# LoRa_ST_Sensor_Node_v1_2.net
KiCad netlist of a schematic drawn in EAGLE
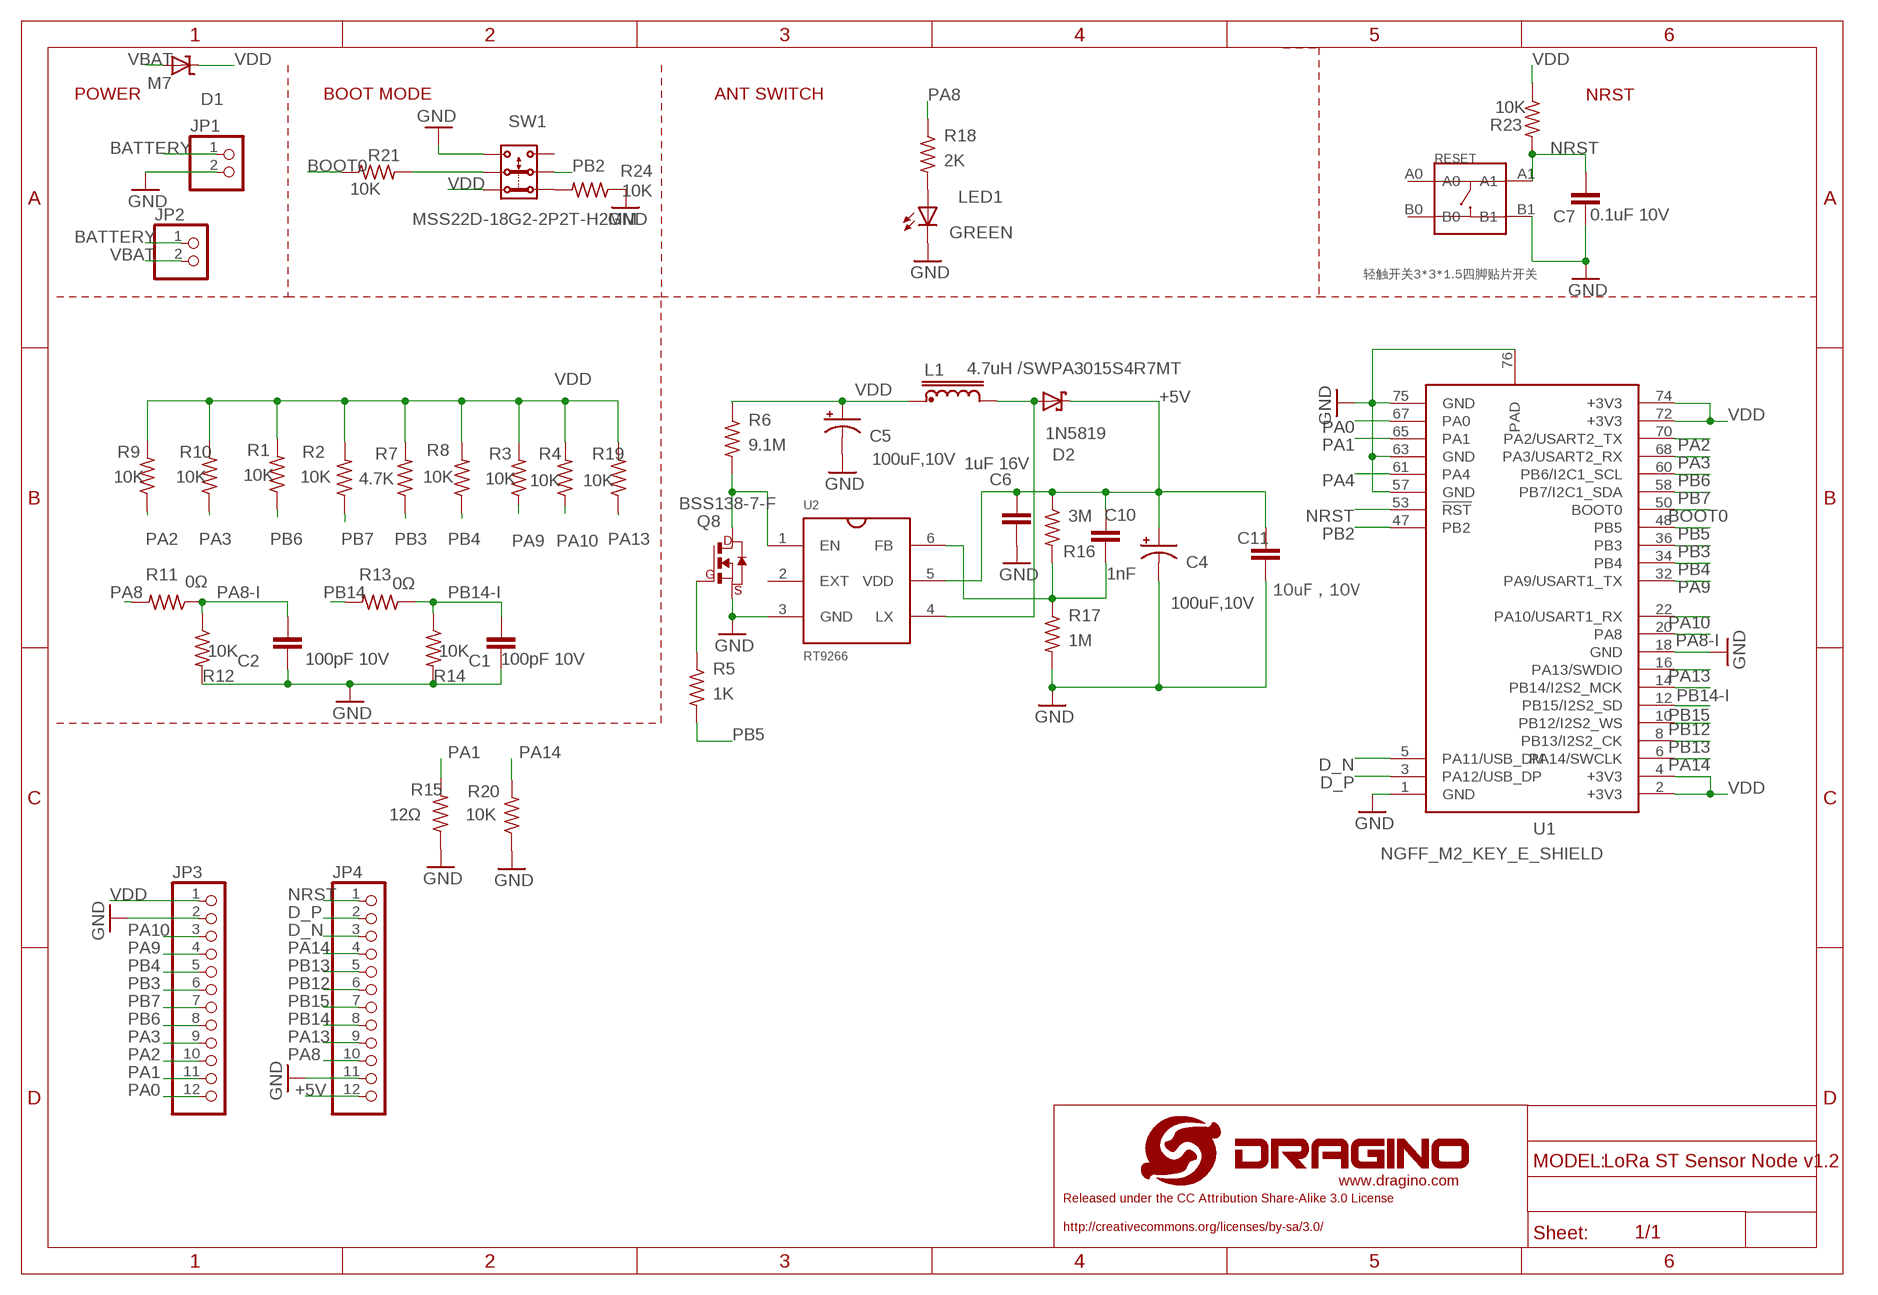
[diagram p0: schematic, sheet 1]

(export (version "E")
  (design (tool "Eeschema 10.0.6"))
  (components
    (comp (ref "C1")
      (value "100pF 10V")
      (footprint "eagle-import:C0603")
      (libsource (lib "eagle-import") (part "C-EUC0603"))
    )
    (comp (ref "C2")
      (value "100pF 10V")
      (footprint "eagle-import:C0603")
      (libsource (lib "eagle-import") (part "C-EUC0603"))
    )
    (comp (ref "C4")
      (value "100uF,10V")
      (footprint "eagle-import:SMC_B")
      (libsource (lib "eagle-import") (part "CPOL-USSMCB"))
    )
    (comp (ref "C5")
      (value "100uF,10V")
      (footprint "eagle-import:SMC_B")
      (libsource (lib "eagle-import") (part "CPOL-USSMCB"))
    )
    (comp (ref "C6")
      (value "1uF 16V")
      (footprint "eagle-import:C0603")
      (libsource (lib "eagle-import") (part "C-EUC0603"))
    )
    (comp (ref "C7")
      (value "0.1uF 10V")
      (footprint "eagle-import:C0402")
      (libsource (lib "eagle-import") (part "C-EUC0402"))
    )
    (comp (ref "C10")
      (value "1nF")
      (footprint "eagle-import:C0402")
      (libsource (lib "eagle-import") (part "C-EUC0402"))
    )
    (comp (ref "C11")
      (value "10uF，10V")
      (footprint "eagle-import:C0805")
      (libsource (lib "eagle-import") (part "dragino-passive_C-EUC0805"))
    )
    (comp (ref "D1")
      (value "M7")
      (footprint "eagle-import:DO214AC")
      (libsource (lib "eagle-import") (part "SCHOTTKYSMBG"))
    )
    (comp (ref "D2")
      (value "1N5819")
      (footprint "eagle-import:SOD123FL")
      (libsource (lib "eagle-import") (part "SMF5.0AT1"))
    )
    (comp (ref "JP1")
      (value "PINHD-1X2L")
      (footprint "eagle-import:XH2.54-2P-L")
      (libsource (lib "eagle-import") (part "PINHD-1X2L"))
    )
    (comp (ref "JP2")
      (value "PINHD-1X2")
      (footprint "eagle-import:1X02")
      (libsource (lib "eagle-import") (part "PINHD-1X2"))
    )
    (comp (ref "JP3")
      (value "PINHD-1X12\"\"")
      (footprint "eagle-import:1X12-DIP")
      (libsource (lib "eagle-import") (part "PINHD-1X12{dblquote}{dblquote}"))
    )
    (comp (ref "JP4")
      (value "PINHD-1X12\"\"")
      (footprint "eagle-import:1X12-DIP")
      (libsource (lib "eagle-import") (part "PINHD-1X12{dblquote}{dblquote}"))
    )
    (comp (ref "L1")
      (value "4.7uH /SWPA3015S4R7MT")
      (footprint "eagle-import:SWPA3010S")
      (libsource (lib "eagle-import") (part "INDUCTORSWPA3010S"))
    )
    (comp (ref "LED1")
      (value "GREEN")
      (footprint "eagle-import:CHIPLED_0603")
      (libsource (lib "eagle-import") (part "LEDCHIPLED_0603"))
    )
    (comp (ref "Q8")
      (value "BSS138-7-F")
      (footprint "eagle-import:SOT-23")
      (libsource (lib "eagle-import") (part "NMOSFET"))
    )
    (comp (ref "R1")
      (value "10K")
      (footprint "eagle-import:R0402")
      (libsource (lib "eagle-import") (part "R-US_R0402"))
    )
    (comp (ref "R2")
      (value "10K")
      (footprint "eagle-import:R0402")
      (libsource (lib "eagle-import") (part "R-US_R0402"))
    )
    (comp (ref "R3")
      (value "10K")
      (footprint "eagle-import:R0402")
      (libsource (lib "eagle-import") (part "R-US_R0402"))
    )
    (comp (ref "R4")
      (value "10K")
      (footprint "eagle-import:R0402")
      (libsource (lib "eagle-import") (part "R-US_R0402"))
    )
    (comp (ref "R5")
      (value "1K")
      (footprint "eagle-import:R0402")
      (libsource (lib "eagle-import") (part "R-US_R0402"))
    )
    (comp (ref "R6")
      (value "9.1M")
      (footprint "eagle-import:R0402")
      (libsource (lib "eagle-import") (part "R-US_R0402"))
    )
    (comp (ref "R7")
      (value "4.7K")
      (footprint "eagle-import:R0402")
      (libsource (lib "eagle-import") (part "R-US_R0402"))
    )
    (comp (ref "R8")
      (value "10K")
      (footprint "eagle-import:R0402")
      (libsource (lib "eagle-import") (part "R-US_R0402"))
    )
    (comp (ref "R9")
      (value "10K")
      (footprint "eagle-import:R0402")
      (libsource (lib "eagle-import") (part "R-US_R0402"))
    )
    (comp (ref "R10")
      (value "10K")
      (footprint "eagle-import:R0402")
      (libsource (lib "eagle-import") (part "R-US_R0402"))
    )
    (comp (ref "R11")
      (value "0Ω")
      (footprint "eagle-import:R0603")
      (libsource (lib "eagle-import") (part "R-US_R0603"))
    )
    (comp (ref "R12")
      (value "10K")
      (footprint "eagle-import:R0603")
      (libsource (lib "eagle-import") (part "R-US_R0603"))
    )
    (comp (ref "R13")
      (value "0Ω")
      (footprint "eagle-import:R0603")
      (libsource (lib "eagle-import") (part "R-US_R0603"))
    )
    (comp (ref "R14")
      (value "10K")
      (footprint "eagle-import:R0603")
      (libsource (lib "eagle-import") (part "R-US_R0603"))
    )
    (comp (ref "R15")
      (value "12Ω")
      (footprint "eagle-import:R1206")
      (libsource (lib "eagle-import") (part "R-US_R1206"))
    )
    (comp (ref "R16")
      (value "3M")
      (footprint "eagle-import:R0402")
      (libsource (lib "eagle-import") (part "R-US_R0402"))
    )
    (comp (ref "R17")
      (value "1M")
      (footprint "eagle-import:R0402")
      (libsource (lib "eagle-import") (part "R-US_R0402"))
    )
    (comp (ref "R18")
      (value "2K")
      (footprint "eagle-import:R0402")
      (libsource (lib "eagle-import") (part "R-US_R0402"))
    )
    (comp (ref "R19")
      (value "10K")
      (footprint "eagle-import:R0402")
      (libsource (lib "eagle-import") (part "R-US_R0402"))
    )
    (comp (ref "R20")
      (value "10K")
      (footprint "eagle-import:R0402")
      (libsource (lib "eagle-import") (part "R-US_R0402"))
    )
    (comp (ref "R21")
      (value "10K")
      (footprint "eagle-import:R0402")
      (libsource (lib "eagle-import") (part "R-US_R0402"))
    )
    (comp (ref "R23")
      (value "10K")
      (footprint "eagle-import:R0402")
      (libsource (lib "eagle-import") (part "R-US_R0402"))
    )
    (comp (ref "R24")
      (value "10K")
      (footprint "eagle-import:R0402")
      (libsource (lib "eagle-import") (part "R-US_R0402"))
    )
    (comp (ref "RESET")
      (value "轻触开关3*3*1.5四脚贴片开关")
      (footprint "eagle-import:SW4-SMD-3.35X3.35X1.5MM")
      (libsource (lib "eagle-import") (part "BUTTON-4P-3.3X3.3"))
    )
    (comp (ref "SW1")
      (value "MSS22D-18G2-2P2T-H2MM")
      (footprint "eagle-import:MSS22D-18G2-2P2T-H2MM-DIL")
      (libsource (lib "eagle-import") (part "MSS22D-18G2-2P2T-H2MM"))
    )
    (comp (ref "U1")
      (value "NGFF_M2_KEY_E_SHIELD")
      (footprint "eagle-import:NGFF_M2_KEY_E_SHIELD")
      (libsource (lib "eagle-import") (part "NGFF_M2_KEY_E_SHIELD"))
    )
    (comp (ref "U2")
      (value "RT9266")
      (footprint "eagle-import:6_SOT-23")
      (libsource (lib "eagle-import") (part "RT9266"))
    )
  )
  (nets
    (net (code "1") (name "/+5V") (class "Default")
      (node (ref "C10") (pin "2") (pinfunction "2_2") (pintype "passive"))
      (node (ref "C11") (pin "2") (pinfunction "2_2") (pintype "passive"))
      (node (ref "C4") (pin "+") (pinfunction "+_+") (pintype "passive"))
      (node (ref "C6") (pin "2") (pinfunction "2_2") (pintype "passive"))
      (node (ref "D2") (pin "C") (pinfunction "C_C") (pintype "passive"))
      (node (ref "JP4") (pin "12") (pinfunction "12_12") (pintype "passive"))
      (node (ref "R16") (pin "1") (pinfunction "1_1") (pintype "passive"))
      (node (ref "U2") (pin "5") (pinfunction "VDD_5") (pintype "bidirectional"))
    )
    (net (code "2") (name "/BATTERY") (class "Default")
      (node (ref "JP1") (pin "1") (pinfunction "1_1") (pintype "passive"))
      (node (ref "JP2") (pin "1") (pinfunction "1_1") (pintype "passive"))
    )
    (net (code "3") (name "/BOOT0") (class "Default")
      (node (ref "R21") (pin "1") (pinfunction "1_1") (pintype "passive"))
      (node (ref "U1") (pin "50") (pinfunction "BOOT0_50") (pintype "bidirectional"))
    )
    (net (code "4") (name "/D_N") (class "Default")
      (node (ref "JP4") (pin "3") (pinfunction "3_3") (pintype "passive"))
      (node (ref "U1") (pin "5") (pinfunction "PA11/USB_DM_5") (pintype "bidirectional"))
    )
    (net (code "5") (name "/D_P") (class "Default")
      (node (ref "JP4") (pin "2") (pinfunction "2_2") (pintype "passive"))
      (node (ref "U1") (pin "3") (pinfunction "PA12/USB_DP_3") (pintype "bidirectional"))
    )
    (net (code "6") (name "/NRST") (class "Default")
      (node (ref "C7") (pin "2") (pinfunction "2_2") (pintype "passive"))
      (node (ref "JP4") (pin "1") (pinfunction "1_1") (pintype "passive"))
      (node (ref "R23") (pin "2") (pinfunction "2_2") (pintype "passive"))
      (node (ref "RESET") (pin "A1") (pinfunction "A1_A1") (pintype "bidirectional"))
      (node (ref "U1") (pin "53") (pinfunction "~{RST}_53") (pintype "bidirectional"))
    )
    (net (code "7") (name "/PA0") (class "Default")
      (node (ref "JP3") (pin "12") (pinfunction "12_12") (pintype "passive"))
      (node (ref "U1") (pin "67") (pinfunction "PA0_67") (pintype "bidirectional"))
    )
    (net (code "8") (name "/PA1") (class "Default")
      (node (ref "JP3") (pin "11") (pinfunction "11_11") (pintype "passive"))
      (node (ref "R15") (pin "2") (pinfunction "2_2") (pintype "passive"))
      (node (ref "U1") (pin "65") (pinfunction "PA1_65") (pintype "bidirectional"))
    )
    (net (code "9") (name "/PA2") (class "Default")
      (node (ref "JP3") (pin "10") (pinfunction "10_10") (pintype "passive"))
      (node (ref "R9") (pin "1") (pinfunction "1_1") (pintype "passive"))
      (node (ref "U1") (pin "70") (pinfunction "PA2/USART2_TX_70") (pintype "bidirectional"))
    )
    (net (code "10") (name "/PA3") (class "Default")
      (node (ref "JP3") (pin "9") (pinfunction "9_9") (pintype "passive"))
      (node (ref "R10") (pin "1") (pinfunction "1_1") (pintype "passive"))
      (node (ref "U1") (pin "68") (pinfunction "PA3/USART2_RX_68") (pintype "bidirectional"))
    )
    (net (code "11") (name "/PA4") (class "Default")
      (node (ref "U1") (pin "61") (pinfunction "PA4_61") (pintype "bidirectional"))
    )
    (net (code "12") (name "/PA8") (class "Default")
      (node (ref "JP4") (pin "10") (pinfunction "10_10") (pintype "passive"))
      (node (ref "R11") (pin "2") (pinfunction "2_2") (pintype "passive"))
      (node (ref "R18") (pin "1") (pinfunction "1_1") (pintype "passive"))
    )
    (net (code "13") (name "/PA8-I") (class "Default")
      (node (ref "C2") (pin "2") (pinfunction "2_2") (pintype "passive"))
      (node (ref "R11") (pin "1") (pinfunction "1_1") (pintype "passive"))
      (node (ref "R12") (pin "1") (pinfunction "1_1") (pintype "passive"))
      (node (ref "U1") (pin "20") (pinfunction "PA8_20") (pintype "bidirectional"))
    )
    (net (code "14") (name "/PA9") (class "Default")
      (node (ref "JP3") (pin "4") (pinfunction "4_4") (pintype "passive"))
      (node (ref "R3") (pin "1") (pinfunction "1_1") (pintype "passive"))
      (node (ref "U1") (pin "32") (pinfunction "PA9/USART1_TX_32") (pintype "bidirectional"))
    )
    (net (code "15") (name "/PA10") (class "Default")
      (node (ref "JP3") (pin "3") (pinfunction "3_3") (pintype "passive"))
      (node (ref "R4") (pin "1") (pinfunction "1_1") (pintype "passive"))
      (node (ref "U1") (pin "22") (pinfunction "PA10/USART1_RX_22") (pintype "bidirectional"))
    )
    (net (code "16") (name "/PA13") (class "Default")
      (node (ref "JP4") (pin "9") (pinfunction "9_9") (pintype "passive"))
      (node (ref "R19") (pin "1") (pinfunction "1_1") (pintype "passive"))
      (node (ref "U1") (pin "16") (pinfunction "PA13/SWDIO_16") (pintype "bidirectional"))
    )
    (net (code "17") (name "/PA14") (class "Default")
      (node (ref "JP4") (pin "4") (pinfunction "4_4") (pintype "passive"))
      (node (ref "R20") (pin "2") (pinfunction "2_2") (pintype "passive"))
      (node (ref "U1") (pin "6") (pinfunction "PA14/SWCLK_6") (pintype "bidirectional"))
    )
    (net (code "18") (name "/PB2") (class "Default")
      (node (ref "SW1") (pin "5") (pinfunction "5_5") (pintype "bidirectional"))
      (node (ref "U1") (pin "47") (pinfunction "PB2_47") (pintype "bidirectional"))
    )
    (net (code "19") (name "/PB3") (class "Default")
      (node (ref "JP3") (pin "6") (pinfunction "6_6") (pintype "passive"))
      (node (ref "R7") (pin "1") (pinfunction "1_1") (pintype "passive"))
      (node (ref "U1") (pin "36") (pinfunction "PB3_36") (pintype "bidirectional"))
    )
    (net (code "20") (name "/PB4") (class "Default")
      (node (ref "JP3") (pin "5") (pinfunction "5_5") (pintype "passive"))
      (node (ref "R8") (pin "1") (pinfunction "1_1") (pintype "passive"))
      (node (ref "U1") (pin "34") (pinfunction "PB4_34") (pintype "bidirectional"))
    )
    (net (code "21") (name "/PB5") (class "Default")
      (node (ref "R5") (pin "2") (pinfunction "2_2") (pintype "passive"))
      (node (ref "U1") (pin "48") (pinfunction "PB5_48") (pintype "bidirectional"))
    )
    (net (code "22") (name "/PB6") (class "Default")
      (node (ref "JP3") (pin "8") (pinfunction "8_8") (pintype "passive"))
      (node (ref "R1") (pin "1") (pinfunction "1_1") (pintype "passive"))
      (node (ref "U1") (pin "60") (pinfunction "PB6/I2C1_SCL_60") (pintype "bidirectional"))
    )
    (net (code "23") (name "/PB7") (class "Default")
      (node (ref "JP3") (pin "7") (pinfunction "7_7") (pintype "passive"))
      (node (ref "R2") (pin "1") (pinfunction "1_1") (pintype "passive"))
      (node (ref "U1") (pin "58") (pinfunction "PB7/I2C1_SDA_58") (pintype "bidirectional"))
    )
    (net (code "24") (name "/PB12") (class "Default")
      (node (ref "JP4") (pin "6") (pinfunction "6_6") (pintype "passive"))
      (node (ref "U1") (pin "10") (pinfunction "PB12/I2S2_WS_10") (pintype "bidirectional"))
    )
    (net (code "25") (name "/PB13") (class "Default")
      (node (ref "JP4") (pin "5") (pinfunction "5_5") (pintype "passive"))
      (node (ref "U1") (pin "8") (pinfunction "PB13/I2S2_CK_8") (pintype "bidirectional"))
    )
    (net (code "26") (name "/PB14") (class "Default")
      (node (ref "JP4") (pin "8") (pinfunction "8_8") (pintype "passive"))
      (node (ref "R13") (pin "2") (pinfunction "2_2") (pintype "passive"))
    )
    (net (code "27") (name "/PB14-I") (class "Default")
      (node (ref "C1") (pin "2") (pinfunction "2_2") (pintype "passive"))
      (node (ref "R13") (pin "1") (pinfunction "1_1") (pintype "passive"))
      (node (ref "R14") (pin "1") (pinfunction "1_1") (pintype "passive"))
      (node (ref "U1") (pin "14") (pinfunction "PB14/I2S2_MCK_14") (pintype "bidirectional"))
    )
    (net (code "28") (name "/PB15") (class "Default")
      (node (ref "JP4") (pin "7") (pinfunction "7_7") (pintype "passive"))
      (node (ref "U1") (pin "12") (pinfunction "PB15/I2S2_SD_12") (pintype "bidirectional"))
    )
    (net (code "29") (name "/VBAT") (class "Default")
      (node (ref "D1") (pin "A") (pinfunction "A_A") (pintype "passive"))
      (node (ref "JP2") (pin "2") (pinfunction "2_2") (pintype "passive"))
    )
    (net (code "30") (name "/VDD") (class "Default")
      (node (ref "C5") (pin "+") (pinfunction "+_+") (pintype "passive"))
      (node (ref "D1") (pin "C") (pinfunction "C_C") (pintype "passive"))
      (node (ref "JP3") (pin "1") (pinfunction "1_1") (pintype "passive"))
      (node (ref "L1") (pin "P$1") (pinfunction "1_P$1") (pintype "passive"))
      (node (ref "R1") (pin "2") (pinfunction "2_2") (pintype "passive"))
      (node (ref "R10") (pin "2") (pinfunction "2_2") (pintype "passive"))
      (node (ref "R19") (pin "2") (pinfunction "2_2") (pintype "passive"))
      (node (ref "R2") (pin "2") (pinfunction "2_2") (pintype "passive"))
      (node (ref "R23") (pin "1") (pinfunction "1_1") (pintype "passive"))
      (node (ref "R3") (pin "2") (pinfunction "2_2") (pintype "passive"))
      (node (ref "R4") (pin "2") (pinfunction "2_2") (pintype "passive"))
      (node (ref "R6") (pin "1") (pinfunction "1_1") (pintype "passive"))
      (node (ref "R7") (pin "2") (pinfunction "2_2") (pintype "passive"))
      (node (ref "R8") (pin "2") (pinfunction "2_2") (pintype "passive"))
      (node (ref "R9") (pin "2") (pinfunction "2_2") (pintype "passive"))
      (node (ref "SW1") (pin "3") (pinfunction "3_3") (pintype "bidirectional"))
      (node (ref "U1") (pin "2") (pinfunction "+3V3_2") (pintype "bidirectional"))
      (node (ref "U1") (pin "4") (pinfunction "+3V3_4") (pintype "bidirectional"))
      (node (ref "U1") (pin "72") (pinfunction "+3V3_72") (pintype "bidirectional"))
      (node (ref "U1") (pin "74") (pinfunction "+3V3_74") (pintype "bidirectional"))
    )
    (net (code "31") (name "GND") (class "Default")
      (node (ref "C1") (pin "1") (pinfunction "1_1") (pintype "passive"))
      (node (ref "C11") (pin "1") (pinfunction "1_1") (pintype "passive"))
      (node (ref "C2") (pin "1") (pinfunction "1_1") (pintype "passive"))
      (node (ref "C4") (pin "-") (pinfunction "-_-") (pintype "passive"))
      (node (ref "C5") (pin "-") (pinfunction "-_-") (pintype "passive"))
      (node (ref "C6") (pin "1") (pinfunction "1_1") (pintype "passive"))
      (node (ref "C7") (pin "1") (pinfunction "1_1") (pintype "passive"))
      (node (ref "JP1") (pin "2") (pinfunction "2_2") (pintype "passive"))
      (node (ref "JP3") (pin "2") (pinfunction "2_2") (pintype "passive"))
      (node (ref "JP4") (pin "11") (pinfunction "11_11") (pintype "passive"))
      (node (ref "LED1") (pin "C") (pinfunction "C_C") (pintype "passive"))
      (node (ref "Q8") (pin "2") (pinfunction "S_2") (pintype "passive"))
      (node (ref "R12") (pin "2") (pinfunction "2_2") (pintype "passive"))
      (node (ref "R14") (pin "2") (pinfunction "2_2") (pintype "passive"))
      (node (ref "R15") (pin "1") (pinfunction "1_1") (pintype "passive"))
      (node (ref "R17") (pin "2") (pinfunction "2_2") (pintype "passive"))
      (node (ref "R20") (pin "1") (pinfunction "1_1") (pintype "passive"))
      (node (ref "R24") (pin "1") (pinfunction "1_1") (pintype "passive"))
      (node (ref "RESET") (pin "B1") (pinfunction "B1_B1") (pintype "bidirectional"))
      (node (ref "SW1") (pin "1") (pinfunction "1_1") (pintype "bidirectional"))
      (node (ref "U1") (pin "1") (pinfunction "GND_1") (pintype "bidirectional"))
      (node (ref "U1") (pin "18") (pinfunction "GND_18") (pintype "bidirectional"))
      (node (ref "U1") (pin "57") (pinfunction "GND_57") (pintype "bidirectional"))
      (node (ref "U1") (pin "63") (pinfunction "GND_63") (pintype "bidirectional"))
      (node (ref "U1") (pin "75") (pinfunction "GND_75") (pintype "bidirectional"))
      (node (ref "U1") (pin "76") (pinfunction "PAD_76") (pintype "bidirectional"))
      (node (ref "U2") (pin "3") (pinfunction "GND_3") (pintype "bidirectional"))
    )
    (net (code "32") (name "Net-(L1-4)") (class "Default")
      (node (ref "D2") (pin "A") (pinfunction "A_A") (pintype "passive"))
      (node (ref "L1") (pin "P$2") (pinfunction "4_P$2") (pintype "passive"))
      (node (ref "U2") (pin "4") (pinfunction "LX_4") (pintype "bidirectional"))
    )
    (net (code "33") (name "Net-(LED1-PadA)") (class "Default")
      (node (ref "LED1") (pin "A") (pinfunction "A_A") (pintype "passive"))
      (node (ref "R18") (pin "2") (pinfunction "2_2") (pintype "passive"))
    )
    (net (code "34") (name "Net-(Q8-D)") (class "Default")
      (node (ref "Q8") (pin "1") (pinfunction "D_1") (pintype "passive"))
      (node (ref "R6") (pin "2") (pinfunction "2_2") (pintype "passive"))
      (node (ref "U2") (pin "1") (pinfunction "EN_1") (pintype "input"))
    )
    (net (code "35") (name "Net-(Q8-G)") (class "Default")
      (node (ref "Q8") (pin "3") (pinfunction "G_3") (pintype "passive"))
      (node (ref "R5") (pin "1") (pinfunction "1_1") (pintype "passive"))
    )
    (net (code "36") (name "Net-(R21-Pad2)") (class "Default")
      (node (ref "R21") (pin "2") (pinfunction "2_2") (pintype "passive"))
      (node (ref "SW1") (pin "2") (pinfunction "2_2") (pintype "bidirectional"))
    )
    (net (code "37") (name "Net-(R24-Pad2)") (class "Default")
      (node (ref "R24") (pin "2") (pinfunction "2_2") (pintype "passive"))
      (node (ref "SW1") (pin "4") (pinfunction "4_4") (pintype "bidirectional"))
    )
    (net (code "38") (name "Net-(U2-FB)") (class "Default")
      (node (ref "C10") (pin "1") (pinfunction "1_1") (pintype "passive"))
      (node (ref "R16") (pin "2") (pinfunction "2_2") (pintype "passive"))
      (node (ref "R17") (pin "1") (pinfunction "1_1") (pintype "passive"))
      (node (ref "U2") (pin "6") (pinfunction "FB_6") (pintype "bidirectional"))
    )
    (net (code "39") (name "unconnected-(RESET-PadA0)") (class "Default")
      (node (ref "RESET") (pin "A0") (pinfunction "A0_A0") (pintype "bidirectional"))
    )
    (net (code "40") (name "unconnected-(RESET-PadB0)") (class "Default")
      (node (ref "RESET") (pin "B0") (pinfunction "B0_B0") (pintype "bidirectional"))
    )
    (net (code "41") (name "unconnected-(SW1-Pad6)") (class "Default")
      (node (ref "SW1") (pin "6") (pinfunction "6_6") (pintype "bidirectional"))
    )
    (net (code "42") (name "unconnected-(U2-EXT-Pad2)") (class "Default")
      (node (ref "U2") (pin "2") (pinfunction "EXT_2") (pintype "bidirectional"))
    )
  )
)
